# STM32F103_407VET6.net
KiCad netlist of a schematic drawn in Altium Designer
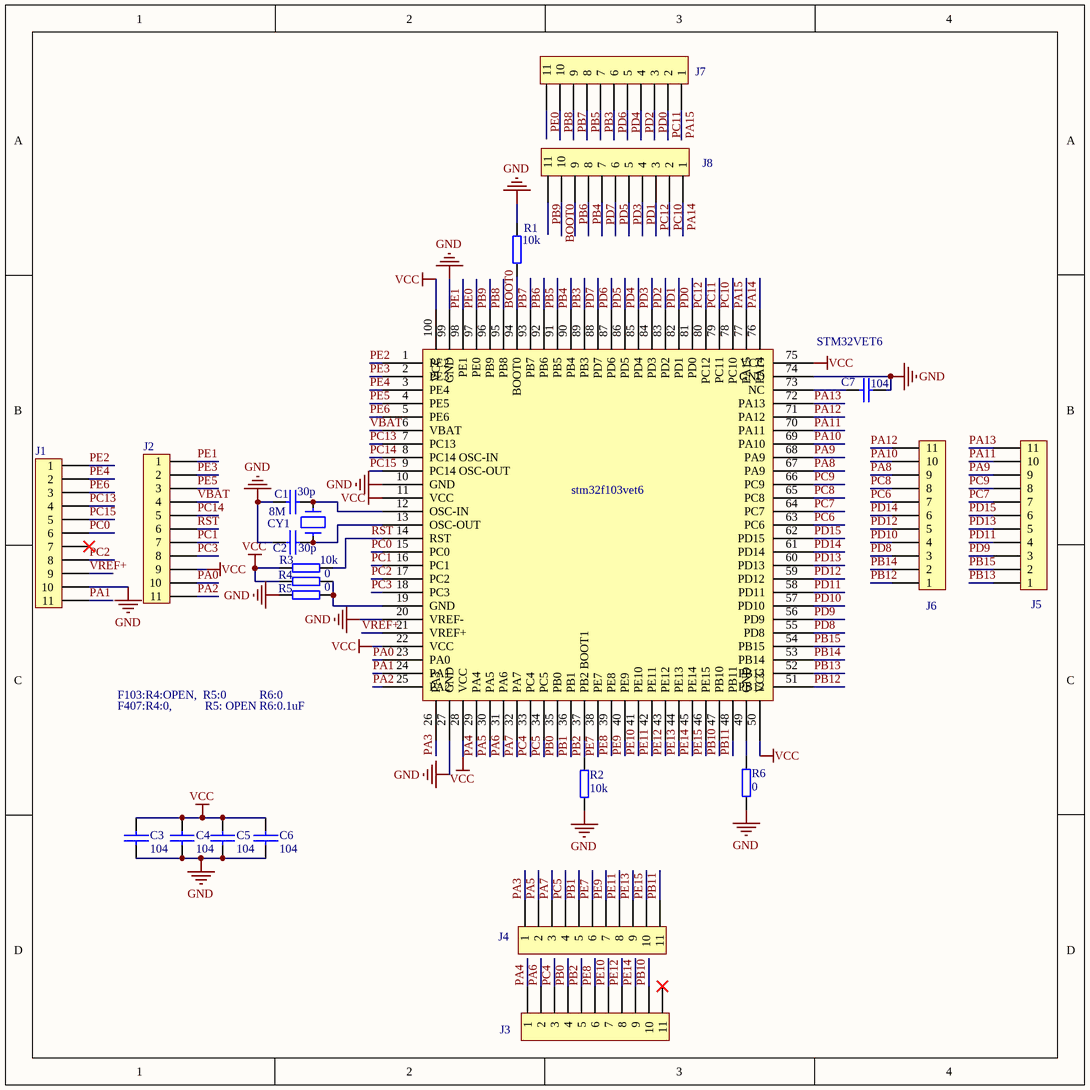
[diagram p0: STM32F103&407VET6.SchDoc]

(export (version "E")
  (design (tool "Eeschema 10.0.6"))
  (components
    (comp (ref "C1") (value "30p") (footprint "0805") (libsource (lib "电容系列") (part "C1")))
    (comp (ref "C2") (value "30p") (footprint "0805") (libsource (lib "电容系列") (part "C1")))
    (comp (ref "C3") (value "104") (footprint "0805") (libsource (lib "电容系列") (part "C1")))
    (comp (ref "C4") (value "104") (footprint "0805") (libsource (lib "电容系列") (part "C1")))
    (comp (ref "C5") (value "104") (footprint "0805") (libsource (lib "电容系列") (part "C1")))
    (comp (ref "C6") (value "104") (footprint "0805") (libsource (lib "电容系列") (part "C1")))
    (comp (ref "C7") (value "104") (footprint "0805") (libsource (lib "电容系列") (part "C1")))
    (comp (ref "CY1") (value "8M") (footprint "CY1") (libsource (lib "常用库") (part "CY1")))
    (comp (ref "J1") (value "CON11") (footprint "SIP11") (libsource (lib "") (part "CON11_2")))
    (comp (ref "J2") (value "CON11") (footprint "SIP11") (libsource (lib "") (part "CON11_2")))
    (comp (ref "J3") (value "CON11") (footprint "SIP11") (libsource (lib "常用接插件") (part "CON11")))
    (comp (ref "J4") (value "CON11") (footprint "SIP11") (libsource (lib "常用接插件") (part "CON11")))
    (comp (ref "J5") (value "CON11") (footprint "SIP11") (libsource (lib "") (part "CON11_3")))
    (comp (ref "J6") (value "CON11") (footprint "SIP11") (libsource (lib "") (part "CON11_3")))
    (comp (ref "J7") (value "CON11") (footprint "SIP11") (libsource (lib "") (part "CON11_1")))
    (comp (ref "J8") (value "CON11") (footprint "SIP11") (libsource (lib "") (part "CON11_1")))
    (comp (ref "R1") (value "10k") (footprint "0805") (libsource (lib "电阻系列") (part "R1")))
    (comp (ref "R2") (value "10k") (footprint "0805") (libsource (lib "电阻系列") (part "R1")))
    (comp (ref "R3") (value "10k") (footprint "0805") (libsource (lib "电阻系列") (part "R1")))
    (comp (ref "R4") (value "0") (footprint "0805") (libsource (lib "电阻系列") (part "R1")))
    (comp (ref "R5") (value "0") (footprint "0805") (libsource (lib "电阻系列") (part "R1")))
    (comp (ref "R6") (value "0") (footprint "0805") (libsource (lib "电阻系列") (part "R1")))
    (comp (ref "STM32VET6")
      (value "Component_1")
      (footprint "TQFP100")
      (libsource (lib "stm32f103vet6") (part "Component_1"))
    )
  )
  (nets
    (net (code "1") (name "/BOOT0") (class "Default")
      (node (ref "J8") (pin "10") (pinfunction "10_10") (pintype "passive"))
      (node (ref "R1") (pin "1") (pinfunction "1_1") (pintype "passive"))
      (node (ref "STM32VET6") (pin "94") (pinfunction "BOOT0_94") (pintype "passive"))
    )
    (net (code "2") (name "/PA0") (class "Default")
      (node (ref "J2") (pin "10") (pinfunction "10_10") (pintype "passive"))
      (node (ref "STM32VET6") (pin "23") (pinfunction "PA0_23") (pintype "passive"))
    )
    (net (code "3") (name "/PA1") (class "Default")
      (node (ref "J1") (pin "11") (pinfunction "11_11") (pintype "passive"))
      (node (ref "STM32VET6") (pin "24") (pinfunction "PA1_24") (pintype "passive"))
    )
    (net (code "4") (name "/PA2") (class "Default")
      (node (ref "J2") (pin "11") (pinfunction "11_11") (pintype "passive"))
      (node (ref "STM32VET6") (pin "25") (pinfunction "PA2_25") (pintype "passive"))
    )
    (net (code "5") (name "/PA3") (class "Default")
      (node (ref "J4") (pin "1") (pinfunction "1_1") (pintype "passive"))
      (node (ref "STM32VET6") (pin "26") (pinfunction "PA3_26") (pintype "passive"))
    )
    (net (code "6") (name "/PA4") (class "Default")
      (node (ref "J3") (pin "1") (pinfunction "1_1") (pintype "passive"))
      (node (ref "STM32VET6") (pin "29") (pinfunction "PA4_29") (pintype "passive"))
    )
    (net (code "7") (name "/PA5") (class "Default")
      (node (ref "J4") (pin "2") (pinfunction "2_2") (pintype "passive"))
      (node (ref "STM32VET6") (pin "30") (pinfunction "PA5_30") (pintype "passive"))
    )
    (net (code "8") (name "/PA6") (class "Default")
      (node (ref "J3") (pin "2") (pinfunction "2_2") (pintype "passive"))
      (node (ref "STM32VET6") (pin "31") (pinfunction "PA6_31") (pintype "passive"))
    )
    (net (code "9") (name "/PA7") (class "Default")
      (node (ref "J4") (pin "3") (pinfunction "3_3") (pintype "passive"))
      (node (ref "STM32VET6") (pin "32") (pinfunction "PA7_32") (pintype "passive"))
    )
    (net (code "10") (name "/PA8") (class "Default")
      (node (ref "J6") (pin "9") (pinfunction "9_9") (pintype "passive"))
      (node (ref "STM32VET6") (pin "67") (pinfunction "PA9_67") (pintype "passive"))
    )
    (net (code "11") (name "/PA9") (class "Default")
      (node (ref "J5") (pin "9") (pinfunction "9_9") (pintype "passive"))
      (node (ref "STM32VET6") (pin "68") (pinfunction "PA9_68") (pintype "passive"))
    )
    (net (code "12") (name "/PA10") (class "Default")
      (node (ref "J6") (pin "10") (pinfunction "10_10") (pintype "passive"))
      (node (ref "STM32VET6") (pin "69") (pinfunction "PA10_69") (pintype "passive"))
    )
    (net (code "13") (name "/PA11") (class "Default")
      (node (ref "J5") (pin "10") (pinfunction "10_10") (pintype "passive"))
      (node (ref "STM32VET6") (pin "70") (pinfunction "PA11_70") (pintype "passive"))
    )
    (net (code "14") (name "/PA12") (class "Default")
      (node (ref "J6") (pin "11") (pinfunction "11_11") (pintype "passive"))
      (node (ref "STM32VET6") (pin "71") (pinfunction "PA12_71") (pintype "passive"))
    )
    (net (code "15") (name "/PA13") (class "Default")
      (node (ref "J5") (pin "11") (pinfunction "11_11") (pintype "passive"))
      (node (ref "STM32VET6") (pin "72") (pinfunction "PA13_72") (pintype "passive"))
    )
    (net (code "16") (name "/PA14") (class "Default")
      (node (ref "J8") (pin "1") (pinfunction "1_1") (pintype "passive"))
      (node (ref "STM32VET6") (pin "76") (pinfunction "PA14_76") (pintype "passive"))
    )
    (net (code "17") (name "/PA15") (class "Default")
      (node (ref "J7") (pin "1") (pinfunction "1_1") (pintype "passive"))
      (node (ref "STM32VET6") (pin "77") (pinfunction "PA15_77") (pintype "passive"))
    )
    (net (code "18") (name "/PB0") (class "Default")
      (node (ref "J3") (pin "4") (pinfunction "4_4") (pintype "passive"))
      (node (ref "STM32VET6") (pin "35") (pinfunction "PB0_35") (pintype "passive"))
    )
    (net (code "19") (name "/PB1") (class "Default")
      (node (ref "J4") (pin "5") (pinfunction "5_5") (pintype "passive"))
      (node (ref "STM32VET6") (pin "36") (pinfunction "PB1_36") (pintype "passive"))
    )
    (net (code "20") (name "/PB2") (class "Default")
      (node (ref "J3") (pin "5") (pinfunction "5_5") (pintype "passive"))
      (node (ref "R2") (pin "2") (pinfunction "2_2") (pintype "passive"))
      (node (ref "STM32VET6") (pin "37") (pinfunction "PB2_BOOT1_37") (pintype "passive"))
    )
    (net (code "21") (name "/PB3") (class "Default")
      (node (ref "J7") (pin "7") (pinfunction "7_7") (pintype "passive"))
      (node (ref "STM32VET6") (pin "89") (pinfunction "PB3_89") (pintype "passive"))
    )
    (net (code "22") (name "/PB4") (class "Default")
      (node (ref "J8") (pin "8") (pinfunction "8_8") (pintype "passive"))
      (node (ref "STM32VET6") (pin "90") (pinfunction "PB4_90") (pintype "passive"))
    )
    (net (code "23") (name "/PB5") (class "Default")
      (node (ref "J7") (pin "8") (pinfunction "8_8") (pintype "passive"))
      (node (ref "STM32VET6") (pin "91") (pinfunction "PB5_91") (pintype "passive"))
    )
    (net (code "24") (name "/PB6") (class "Default")
      (node (ref "J8") (pin "9") (pinfunction "9_9") (pintype "passive"))
      (node (ref "STM32VET6") (pin "92") (pinfunction "PB6_92") (pintype "passive"))
    )
    (net (code "25") (name "/PB7") (class "Default")
      (node (ref "J7") (pin "9") (pinfunction "9_9") (pintype "passive"))
      (node (ref "STM32VET6") (pin "93") (pinfunction "PB7_93") (pintype "passive"))
    )
    (net (code "26") (name "/PB8") (class "Default")
      (node (ref "J7") (pin "10") (pinfunction "10_10") (pintype "passive"))
      (node (ref "STM32VET6") (pin "95") (pinfunction "PB8_95") (pintype "passive"))
    )
    (net (code "27") (name "/PB9") (class "Default")
      (node (ref "J8") (pin "11") (pinfunction "11_11") (pintype "passive"))
      (node (ref "STM32VET6") (pin "96") (pinfunction "PB9_96") (pintype "passive"))
    )
    (net (code "28") (name "/PB10") (class "Default")
      (node (ref "J3") (pin "10") (pinfunction "10_10") (pintype "passive"))
      (node (ref "STM32VET6") (pin "47") (pinfunction "PB10_47") (pintype "passive"))
    )
    (net (code "29") (name "/PB11") (class "Default")
      (node (ref "J4") (pin "11") (pinfunction "11_11") (pintype "passive"))
      (node (ref "STM32VET6") (pin "48") (pinfunction "PB11_48") (pintype "passive"))
    )
    (net (code "30") (name "/PB12") (class "Default")
      (node (ref "J6") (pin "1") (pinfunction "1_1") (pintype "passive"))
      (node (ref "STM32VET6") (pin "51") (pinfunction "PB12_51") (pintype "passive"))
    )
    (net (code "31") (name "/PB13") (class "Default")
      (node (ref "J5") (pin "1") (pinfunction "1_1") (pintype "passive"))
      (node (ref "STM32VET6") (pin "52") (pinfunction "PB13_52") (pintype "passive"))
    )
    (net (code "32") (name "/PB14") (class "Default")
      (node (ref "J6") (pin "2") (pinfunction "2_2") (pintype "passive"))
      (node (ref "STM32VET6") (pin "53") (pinfunction "PB14_53") (pintype "passive"))
    )
    (net (code "33") (name "/PB15") (class "Default")
      (node (ref "J5") (pin "2") (pinfunction "2_2") (pintype "passive"))
      (node (ref "STM32VET6") (pin "54") (pinfunction "PB15_54") (pintype "passive"))
    )
    (net (code "34") (name "/PC0") (class "Default")
      (node (ref "J1") (pin "6") (pinfunction "6_6") (pintype "passive"))
      (node (ref "STM32VET6") (pin "15") (pinfunction "PC0_15") (pintype "passive"))
    )
    (net (code "35") (name "/PC1") (class "Default")
      (node (ref "J2") (pin "7") (pinfunction "7_7") (pintype "passive"))
      (node (ref "STM32VET6") (pin "16") (pinfunction "PC1_16") (pintype "passive"))
    )
    (net (code "36") (name "/PC2") (class "Default")
      (node (ref "J1") (pin "8") (pinfunction "8_8") (pintype "passive"))
      (node (ref "STM32VET6") (pin "17") (pinfunction "PC2_17") (pintype "passive"))
    )
    (net (code "37") (name "/PC3") (class "Default")
      (node (ref "J2") (pin "8") (pinfunction "8_8") (pintype "passive"))
      (node (ref "STM32VET6") (pin "18") (pinfunction "PC3_18") (pintype "passive"))
    )
    (net (code "38") (name "/PC4") (class "Default")
      (node (ref "J3") (pin "3") (pinfunction "3_3") (pintype "passive"))
      (node (ref "STM32VET6") (pin "33") (pinfunction "PC4_33") (pintype "passive"))
    )
    (net (code "39") (name "/PC5") (class "Default")
      (node (ref "J4") (pin "4") (pinfunction "4_4") (pintype "passive"))
      (node (ref "STM32VET6") (pin "34") (pinfunction "PC5_34") (pintype "passive"))
    )
    (net (code "40") (name "/PC6") (class "Default")
      (node (ref "J6") (pin "7") (pinfunction "7_7") (pintype "passive"))
      (node (ref "STM32VET6") (pin "63") (pinfunction "PC6_63") (pintype "passive"))
    )
    (net (code "41") (name "/PC7") (class "Default")
      (node (ref "J5") (pin "7") (pinfunction "7_7") (pintype "passive"))
      (node (ref "STM32VET6") (pin "64") (pinfunction "PC7_64") (pintype "passive"))
    )
    (net (code "42") (name "/PC8") (class "Default")
      (node (ref "J6") (pin "8") (pinfunction "8_8") (pintype "passive"))
      (node (ref "STM32VET6") (pin "65") (pinfunction "PC8_65") (pintype "passive"))
    )
    (net (code "43") (name "/PC9") (class "Default")
      (node (ref "J5") (pin "8") (pinfunction "8_8") (pintype "passive"))
      (node (ref "STM32VET6") (pin "66") (pinfunction "PC9_66") (pintype "passive"))
    )
    (net (code "44") (name "/PC10") (class "Default")
      (node (ref "J8") (pin "2") (pinfunction "2_2") (pintype "passive"))
      (node (ref "STM32VET6") (pin "78") (pinfunction "PC10_78") (pintype "passive"))
    )
    (net (code "45") (name "/PC11") (class "Default")
      (node (ref "J7") (pin "2") (pinfunction "2_2") (pintype "passive"))
      (node (ref "STM32VET6") (pin "79") (pinfunction "PC11_79") (pintype "passive"))
    )
    (net (code "46") (name "/PC12") (class "Default")
      (node (ref "J8") (pin "3") (pinfunction "3_3") (pintype "passive"))
      (node (ref "STM32VET6") (pin "80") (pinfunction "PC12_80") (pintype "passive"))
    )
    (net (code "47") (name "/PC13") (class "Default")
      (node (ref "J1") (pin "4") (pinfunction "4_4") (pintype "passive"))
      (node (ref "STM32VET6") (pin "7") (pinfunction "PC13_7") (pintype "passive"))
    )
    (net (code "48") (name "/PC14") (class "Default")
      (node (ref "J2") (pin "5") (pinfunction "5_5") (pintype "passive"))
      (node (ref "STM32VET6") (pin "8") (pinfunction "PC14_OSC-IN_8") (pintype "passive"))
    )
    (net (code "49") (name "/PC15") (class "Default")
      (node (ref "J1") (pin "5") (pinfunction "5_5") (pintype "passive"))
      (node (ref "STM32VET6") (pin "9") (pinfunction "PC14_OSC-OUT_9") (pintype "passive"))
    )
    (net (code "50") (name "/PD0") (class "Default")
      (node (ref "J7") (pin "3") (pinfunction "3_3") (pintype "passive"))
      (node (ref "STM32VET6") (pin "81") (pinfunction "PD0_81") (pintype "passive"))
    )
    (net (code "51") (name "/PD1") (class "Default")
      (node (ref "J8") (pin "4") (pinfunction "4_4") (pintype "passive"))
      (node (ref "STM32VET6") (pin "82") (pinfunction "PD1_82") (pintype "passive"))
    )
    (net (code "52") (name "/PD2") (class "Default")
      (node (ref "J7") (pin "4") (pinfunction "4_4") (pintype "passive"))
      (node (ref "STM32VET6") (pin "83") (pinfunction "PD2_83") (pintype "passive"))
    )
    (net (code "53") (name "/PD3") (class "Default")
      (node (ref "J8") (pin "5") (pinfunction "5_5") (pintype "passive"))
      (node (ref "STM32VET6") (pin "84") (pinfunction "PD3_84") (pintype "passive"))
    )
    (net (code "54") (name "/PD4") (class "Default")
      (node (ref "J7") (pin "5") (pinfunction "5_5") (pintype "passive"))
      (node (ref "STM32VET6") (pin "85") (pinfunction "PD4_85") (pintype "passive"))
    )
    (net (code "55") (name "/PD5") (class "Default")
      (node (ref "J8") (pin "6") (pinfunction "6_6") (pintype "passive"))
      (node (ref "STM32VET6") (pin "86") (pinfunction "PD5_86") (pintype "passive"))
    )
    (net (code "56") (name "/PD6") (class "Default")
      (node (ref "J7") (pin "6") (pinfunction "6_6") (pintype "passive"))
      (node (ref "STM32VET6") (pin "87") (pinfunction "PD6_87") (pintype "passive"))
    )
    (net (code "57") (name "/PD7") (class "Default")
      (node (ref "J8") (pin "7") (pinfunction "7_7") (pintype "passive"))
      (node (ref "STM32VET6") (pin "88") (pinfunction "PD7_88") (pintype "passive"))
    )
    (net (code "58") (name "/PD8") (class "Default")
      (node (ref "J6") (pin "3") (pinfunction "3_3") (pintype "passive"))
      (node (ref "STM32VET6") (pin "55") (pinfunction "PD8_55") (pintype "passive"))
    )
    (net (code "59") (name "/PD9") (class "Default")
      (node (ref "J5") (pin "3") (pinfunction "3_3") (pintype "passive"))
      (node (ref "STM32VET6") (pin "56") (pinfunction "PD9_56") (pintype "passive"))
    )
    (net (code "60") (name "/PD10") (class "Default")
      (node (ref "J6") (pin "4") (pinfunction "4_4") (pintype "passive"))
      (node (ref "STM32VET6") (pin "57") (pinfunction "PD10_57") (pintype "passive"))
    )
    (net (code "61") (name "/PD11") (class "Default")
      (node (ref "J5") (pin "4") (pinfunction "4_4") (pintype "passive"))
      (node (ref "STM32VET6") (pin "58") (pinfunction "PD11_58") (pintype "passive"))
    )
    (net (code "62") (name "/PD12") (class "Default")
      (node (ref "J6") (pin "5") (pinfunction "5_5") (pintype "passive"))
      (node (ref "STM32VET6") (pin "59") (pinfunction "PD12_59") (pintype "passive"))
    )
    (net (code "63") (name "/PD13") (class "Default")
      (node (ref "J5") (pin "5") (pinfunction "5_5") (pintype "passive"))
      (node (ref "STM32VET6") (pin "60") (pinfunction "PD13_60") (pintype "passive"))
    )
    (net (code "64") (name "/PD14") (class "Default")
      (node (ref "J6") (pin "6") (pinfunction "6_6") (pintype "passive"))
      (node (ref "STM32VET6") (pin "61") (pinfunction "PD14_61") (pintype "passive"))
    )
    (net (code "65") (name "/PD15") (class "Default")
      (node (ref "J5") (pin "6") (pinfunction "6_6") (pintype "passive"))
      (node (ref "STM32VET6") (pin "62") (pinfunction "PD15_62") (pintype "passive"))
    )
    (net (code "66") (name "/PE0") (class "Default")
      (node (ref "J7") (pin "11") (pinfunction "11_11") (pintype "passive"))
      (node (ref "STM32VET6") (pin "97") (pinfunction "PE0_97") (pintype "passive"))
    )
    (net (code "67") (name "/PE1") (class "Default")
      (node (ref "J2") (pin "1") (pinfunction "1_1") (pintype "passive"))
      (node (ref "STM32VET6") (pin "98") (pinfunction "PE1_98") (pintype "passive"))
    )
    (net (code "68") (name "/PE2") (class "Default")
      (node (ref "J1") (pin "1") (pinfunction "1_1") (pintype "passive"))
      (node (ref "STM32VET6") (pin "1") (pinfunction "PE2_1") (pintype "passive"))
    )
    (net (code "69") (name "/PE3") (class "Default")
      (node (ref "J2") (pin "2") (pinfunction "2_2") (pintype "passive"))
      (node (ref "STM32VET6") (pin "2") (pinfunction "PE3_2") (pintype "passive"))
    )
    (net (code "70") (name "/PE4") (class "Default")
      (node (ref "J1") (pin "2") (pinfunction "2_2") (pintype "passive"))
      (node (ref "STM32VET6") (pin "3") (pinfunction "PE4_3") (pintype "passive"))
    )
    (net (code "71") (name "/PE5") (class "Default")
      (node (ref "J2") (pin "3") (pinfunction "3_3") (pintype "passive"))
      (node (ref "STM32VET6") (pin "4") (pinfunction "PE5_4") (pintype "passive"))
    )
    (net (code "72") (name "/PE6") (class "Default")
      (node (ref "J1") (pin "3") (pinfunction "3_3") (pintype "passive"))
      (node (ref "STM32VET6") (pin "5") (pinfunction "PE6_5") (pintype "passive"))
    )
    (net (code "73") (name "/PE7") (class "Default")
      (node (ref "J4") (pin "6") (pinfunction "6_6") (pintype "passive"))
      (node (ref "STM32VET6") (pin "38") (pinfunction "PE7_38") (pintype "passive"))
    )
    (net (code "74") (name "/PE8") (class "Default")
      (node (ref "J3") (pin "6") (pinfunction "6_6") (pintype "passive"))
      (node (ref "STM32VET6") (pin "39") (pinfunction "PE8_39") (pintype "passive"))
    )
    (net (code "75") (name "/PE9") (class "Default")
      (node (ref "J4") (pin "7") (pinfunction "7_7") (pintype "passive"))
      (node (ref "STM32VET6") (pin "40") (pinfunction "PE9_40") (pintype "passive"))
    )
    (net (code "76") (name "/PE10") (class "Default")
      (node (ref "J3") (pin "7") (pinfunction "7_7") (pintype "passive"))
      (node (ref "STM32VET6") (pin "41") (pinfunction "PE10_41") (pintype "passive"))
    )
    (net (code "77") (name "/PE11") (class "Default")
      (node (ref "J4") (pin "8") (pinfunction "8_8") (pintype "passive"))
      (node (ref "STM32VET6") (pin "42") (pinfunction "PE11_42") (pintype "passive"))
    )
    (net (code "78") (name "/PE12") (class "Default")
      (node (ref "J3") (pin "8") (pinfunction "8_8") (pintype "passive"))
      (node (ref "STM32VET6") (pin "43") (pinfunction "PE12_43") (pintype "passive"))
    )
    (net (code "79") (name "/PE13") (class "Default")
      (node (ref "J4") (pin "9") (pinfunction "9_9") (pintype "passive"))
      (node (ref "STM32VET6") (pin "44") (pinfunction "PE13_44") (pintype "passive"))
    )
    (net (code "80") (name "/PE14") (class "Default")
      (node (ref "J3") (pin "9") (pinfunction "9_9") (pintype "passive"))
      (node (ref "STM32VET6") (pin "45") (pinfunction "PE14_45") (pintype "passive"))
    )
    (net (code "81") (name "/PE15") (class "Default")
      (node (ref "J4") (pin "10") (pinfunction "10_10") (pintype "passive"))
      (node (ref "STM32VET6") (pin "46") (pinfunction "PE15_46") (pintype "passive"))
    )
    (net (code "82") (name "/RST") (class "Default")
      (node (ref "J2") (pin "6") (pinfunction "6_6") (pintype "passive"))
      (node (ref "R3") (pin "1") (pinfunction "1_1") (pintype "passive"))
      (node (ref "STM32VET6") (pin "14") (pinfunction "RST_14") (pintype "passive"))
    )
    (net (code "83") (name "/VBAT") (class "Default")
      (node (ref "J2") (pin "4") (pinfunction "4_4") (pintype "passive"))
      (node (ref "STM32VET6") (pin "6") (pinfunction "VBAT_6") (pintype "passive"))
    )
    (net (code "84") (name "/VREF+") (class "Default")
      (node (ref "J1") (pin "9") (pinfunction "9_9") (pintype "passive"))
      (node (ref "STM32VET6") (pin "21") (pinfunction "VREF+_21") (pintype "passive"))
    )
    (net (code "85") (name "GND") (class "Default")
      (node (ref "C1") (pin "2") (pinfunction "2_2") (pintype "passive"))
      (node (ref "C2") (pin "2") (pinfunction "2_2") (pintype "passive"))
      (node (ref "C3") (pin "1") (pinfunction "1_1") (pintype "passive"))
      (node (ref "C4") (pin "2") (pinfunction "2_2") (pintype "passive"))
      (node (ref "C5") (pin "2") (pinfunction "2_2") (pintype "passive"))
      (node (ref "C6") (pin "2") (pinfunction "2_2") (pintype "passive"))
      (node (ref "C7") (pin "1") (pinfunction "1_1") (pintype "passive"))
      (node (ref "J1") (pin "10") (pinfunction "10_10") (pintype "passive"))
      (node (ref "R1") (pin "2") (pinfunction "2_2") (pintype "passive"))
      (node (ref "R2") (pin "1") (pinfunction "1_1") (pintype "passive"))
      (node (ref "R5") (pin "2") (pinfunction "2_2") (pintype "passive"))
      (node (ref "R6") (pin "2") (pinfunction "2_2") (pintype "passive"))
      (node (ref "STM32VET6") (pin "10") (pinfunction "GND_10") (pintype "passive"))
      (node (ref "STM32VET6") (pin "20") (pinfunction "VREF-_20") (pintype "passive"))
      (node (ref "STM32VET6") (pin "27") (pinfunction "GND_27") (pintype "passive"))
      (node (ref "STM32VET6") (pin "74") (pinfunction "GND_74") (pintype "passive"))
      (node (ref "STM32VET6") (pin "99") (pinfunction "GND_99") (pintype "passive"))
    )
    (net (code "86") (name "Net-(R4-Pad1)") (class "Default")
      (node (ref "R4") (pin "1") (pinfunction "1_1") (pintype "passive"))
      (node (ref "R5") (pin "1") (pinfunction "1_1") (pintype "passive"))
      (node (ref "STM32VET6") (pin "19") (pinfunction "GND_19") (pintype "passive"))
    )
    (net (code "87") (name "Net-(R6-Pad1)") (class "Default")
      (node (ref "R6") (pin "1") (pinfunction "1_1") (pintype "passive"))
      (node (ref "STM32VET6") (pin "49") (pinfunction "GND_49") (pintype "passive"))
    )
    (net (code "88") (name "Net-(STM32VET6-NC)") (class "Default")
      (node (ref "C7") (pin "2") (pinfunction "2_2") (pintype "passive"))
      (node (ref "STM32VET6") (pin "73") (pinfunction "NC_73") (pintype "passive"))
    )
    (net (code "89") (name "Net-(STM32VET6-OSC-IN)") (class "Default")
      (node (ref "C1") (pin "1") (pinfunction "1_1") (pintype "passive"))
      (node (ref "CY1") (pin "2") (pinfunction "2_2") (pintype "passive"))
      (node (ref "STM32VET6") (pin "12") (pinfunction "OSC-IN_12") (pintype "passive"))
    )
    (net (code "90") (name "Net-(STM32VET6-OSC-OUT)") (class "Default")
      (node (ref "C2") (pin "1") (pinfunction "1_1") (pintype "passive"))
      (node (ref "CY1") (pin "1") (pinfunction "1_1") (pintype "passive"))
      (node (ref "STM32VET6") (pin "13") (pinfunction "OSC-OUT_13") (pintype "passive"))
    )
    (net (code "91") (name "VCC") (class "Default")
      (node (ref "C3") (pin "2") (pinfunction "2_2") (pintype "passive"))
      (node (ref "C4") (pin "1") (pinfunction "1_1") (pintype "passive"))
      (node (ref "C5") (pin "1") (pinfunction "1_1") (pintype "passive"))
      (node (ref "C6") (pin "1") (pinfunction "1_1") (pintype "passive"))
      (node (ref "J2") (pin "9") (pinfunction "9_9") (pintype "passive"))
      (node (ref "R3") (pin "2") (pinfunction "2_2") (pintype "passive"))
      (node (ref "R4") (pin "2") (pinfunction "2_2") (pintype "passive"))
      (node (ref "STM32VET6") (pin "100") (pinfunction "VCC_100") (pintype "passive"))
      (node (ref "STM32VET6") (pin "11") (pinfunction "VCC_11") (pintype "passive"))
      (node (ref "STM32VET6") (pin "22") (pinfunction "VCC_22") (pintype "passive"))
      (node (ref "STM32VET6") (pin "28") (pinfunction "VCC_28") (pintype "passive"))
      (node (ref "STM32VET6") (pin "50") (pinfunction "VCC_50") (pintype "passive"))
      (node (ref "STM32VET6") (pin "75") (pinfunction "VCC_75") (pintype "passive"))
    )
    (net (code "92") (name "unconnected-(J1-Pad7)") (class "Default")
      (node (ref "J1") (pin "7") (pinfunction "7_7") (pintype "passive+no_connect"))
    )
    (net (code "93") (name "unconnected-(J3-Pad11)") (class "Default")
      (node (ref "J3") (pin "11") (pinfunction "11_11") (pintype "passive+no_connect"))
    )
  )
)
